# 12V_board.net
KiCad netlist of a schematic drawn in Altium Designer
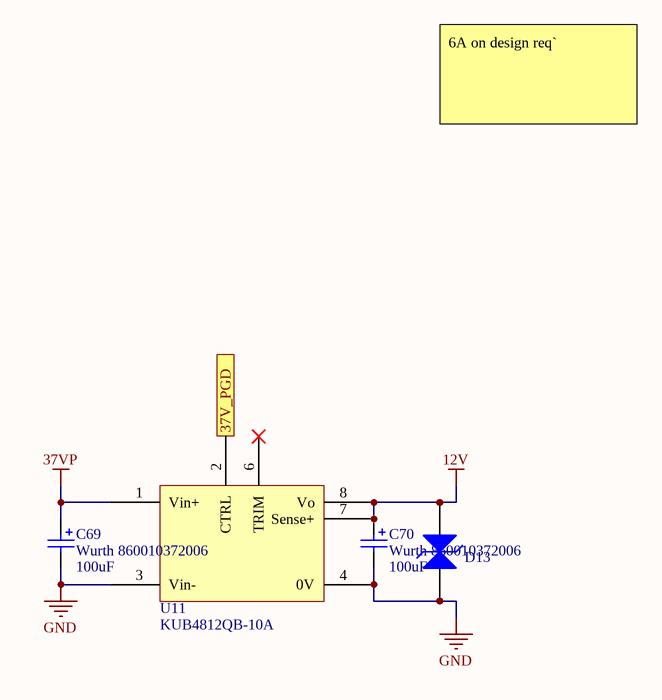
[diagram p0: 12V_board.SchDoc]

(export (version "E")
  (design (tool "Eeschema 10.0.6"))
  (components
    (comp (ref "C69")
      (value "Wurth 860010372006")
      (footprint "Wurth 860010372006")
      (description "Polarized Capacitor (Radial)")
      (fields (field (name "ALTIUM_VALUE") "100uF"))
      (libsource (lib "RSX_Capacitors") (part "Wurth 860010372006"))
    )
    (comp (ref "C70")
      (value "Wurth 860010372006")
      (footprint "Wurth 860010372006")
      (description "Polarized Capacitor (Radial)")
      (fields (field (name "ALTIUM_VALUE") "100uF"))
      (libsource (lib "RSX_Capacitors") (part "Wurth 860010372006"))
    )
    (comp (ref "D13")
      (value "TVS_DIODE")
      (footprint "SMBJ54A-13-F")
      (description "TVS Diode")
      (fields (field (name "PUBLISHER") "Altium Limited"))
      (libsource (lib "RSX_Diodes") (part "TVS_DIODE"))
    )
    (comp (ref "U11")
      (value "KUB4812QB-10A")
      (footprint "KUB48XXQB-10A")
      (description "12V 10A DC DC step down")
      (libsource (lib "RSX_ICs") (part "KUB4812QB-10A"))
    )
  )
  (nets
    (net (code "1") (name "/37V_PGD") (class "Default")
      (node (ref "U11") (pin "2") (pinfunction "CTRL_2") (pintype "passive"))
    )
    (net (code "2") (name "12V") (class "Default")
      (node (ref "C70") (pin "1") (pinfunction "1_1") (pintype "passive"))
      (node (ref "D13") (pin "1") (pinfunction "A_1") (pintype "passive"))
      (node (ref "U11") (pin "7") (pinfunction "Sense+_7") (pintype "passive"))
      (node (ref "U11") (pin "8") (pinfunction "Vo_8") (pintype "passive"))
    )
    (net (code "3") (name "37VP") (class "Default")
      (node (ref "C69") (pin "1") (pinfunction "1_1") (pintype "passive"))
      (node (ref "U11") (pin "1") (pinfunction "Vin+_1") (pintype "passive"))
    )
    (net (code "4") (name "GND") (class "Default")
      (node (ref "C69") (pin "2") (pinfunction "2_2") (pintype "passive"))
      (node (ref "C70") (pin "2") (pinfunction "2_2") (pintype "passive"))
      (node (ref "D13") (pin "2") (pinfunction "K_2") (pintype "passive"))
      (node (ref "U11") (pin "3") (pinfunction "Vin-_3") (pintype "passive"))
      (node (ref "U11") (pin "4") (pinfunction "0V_4") (pintype "passive"))
    )
    (net (code "5") (name "unconnected-(U11-TRIM-Pad6)") (class "Default")
      (node (ref "U11") (pin "6") (pinfunction "TRIM_6") (pintype "passive+no_connect"))
    )
  )
)
